# IMU_07_21_2017.net
KiCad netlist of a schematic drawn in EAGLE
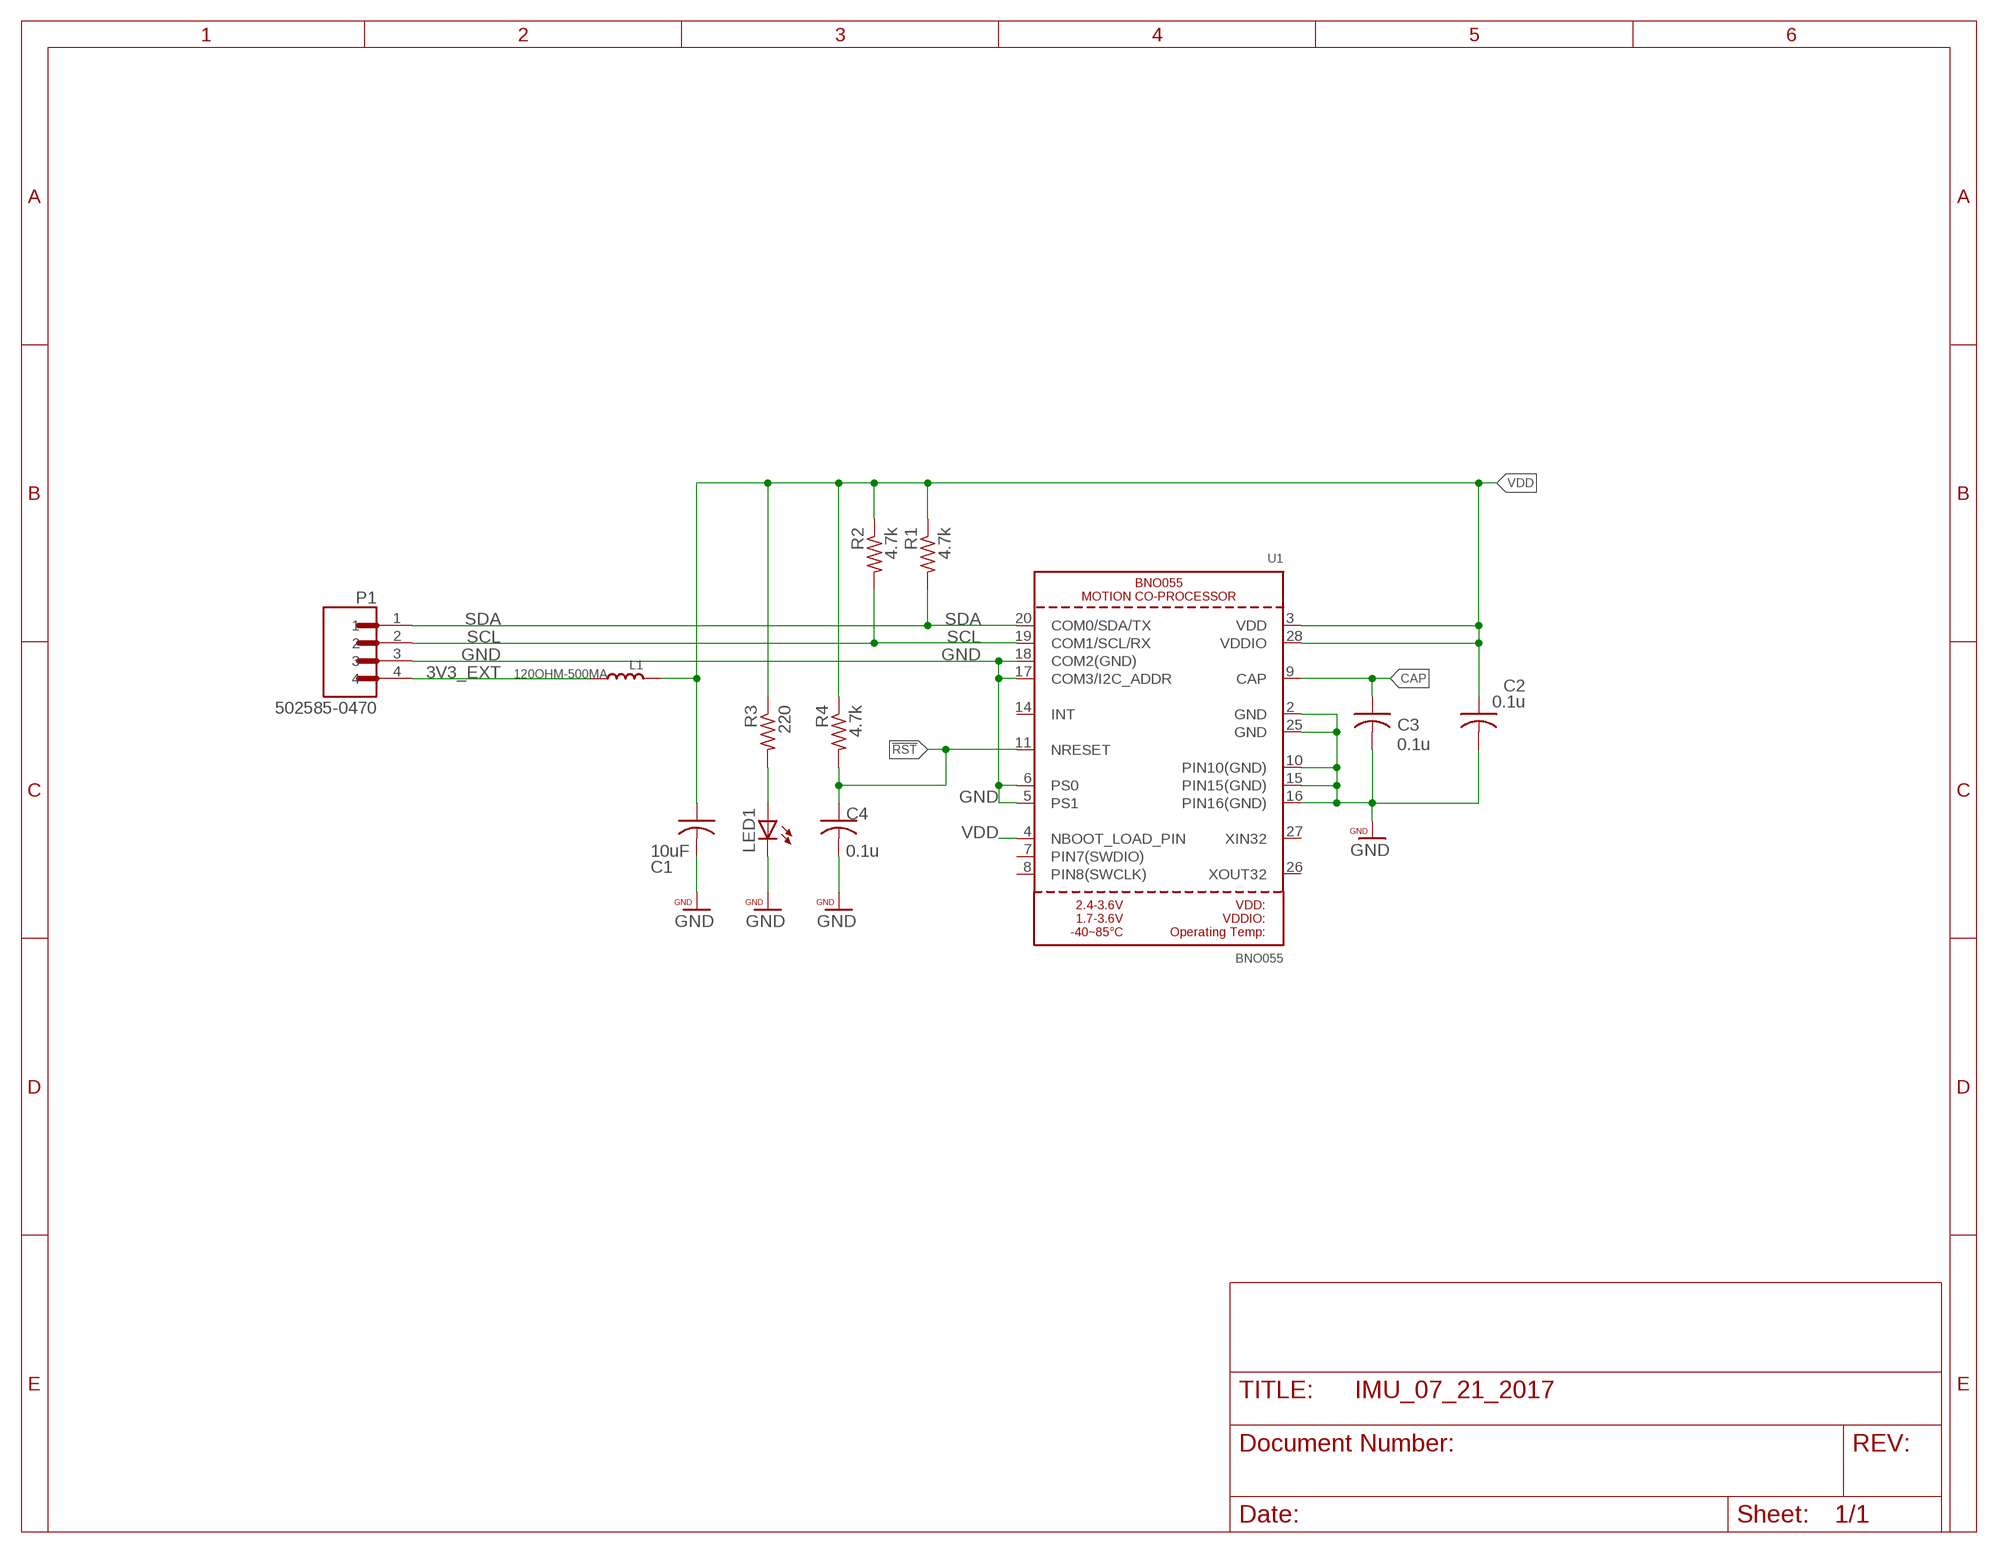
[diagram p0: schematic, sheet 1]

(export (version "E")
  (design (tool "Eeschema 10.0.6"))
  (components
    (comp (ref "C1")
      (value "10uF")
      (footprint "eagle-import:C0402")
      (libsource (lib "eagle-import") (part "C-USC0402"))
    )
    (comp (ref "C2")
      (value "0.1u")
      (footprint "eagle-import:C0402")
      (libsource (lib "eagle-import") (part "C-USC0402"))
    )
    (comp (ref "C3")
      (value "0.1u")
      (footprint "eagle-import:C0402")
      (libsource (lib "eagle-import") (part "C-USC0402"))
    )
    (comp (ref "C4")
      (value "0.1u")
      (footprint "eagle-import:C0402")
      (libsource (lib "eagle-import") (part "C-USC0402"))
    )
    (comp (ref "L1")
      (value "120OHM-500MA")
      (footprint "eagle-import:L0603")
      (fields (field (name "MPN") "BLM18AG121SN1D"))
      (libsource (lib "eagle-import") (part "SMD-FERRITE-CHIP-120-OHM-500MA(0603)"))
    )
    (comp (ref "LED1")
      (value "LEDCHIP-LED0603")
      (footprint "eagle-import:CHIP-LED0603")
      (libsource (lib "eagle-import") (part "LEDCHIP-LED0603"))
    )
    (comp (ref "P1")
      (value "502585-0470")
      (footprint "eagle-import:MOLEX_502585-0470")
      (fields (field (name "MF") "Molex"))
      (libsource (lib "eagle-import") (part "502585-0470"))
    )
    (comp (ref "R1")
      (value "4.7k")
      (footprint "eagle-import:R0402")
      (libsource (lib "eagle-import") (part "R-US_R0402"))
    )
    (comp (ref "R2")
      (value "4.7k")
      (footprint "eagle-import:R0402")
      (libsource (lib "eagle-import") (part "R-US_R0402"))
    )
    (comp (ref "R3")
      (value "220")
      (footprint "eagle-import:R0402")
      (libsource (lib "eagle-import") (part "R-US_R0402"))
    )
    (comp (ref "R4")
      (value "4.7k")
      (footprint "eagle-import:R0402")
      (libsource (lib "eagle-import") (part "R-US_R0402"))
    )
    (comp (ref "U1")
      (value "BNO055")
      (footprint "eagle-import:BNO055")
      (libsource (lib "eagle-import") (part "BNO055"))
    )
  )
  (nets
    (net (code "1") (name "/3V3_EXT") (class "Default")
      (node (ref "L1") (pin "2") (pinfunction "2_2") (pintype "passive"))
      (node (ref "P1") (pin "4") (pinfunction "4_4") (pintype "passive"))
    )
    (net (code "2") (name "/SCL") (class "Default")
      (node (ref "P1") (pin "2") (pinfunction "2_2") (pintype "passive"))
      (node (ref "R2") (pin "2") (pinfunction "2_2") (pintype "passive"))
      (node (ref "U1") (pin "19") (pinfunction "COM1/SCL/RX_19") (pintype "bidirectional"))
    )
    (net (code "3") (name "/SDA") (class "Default")
      (node (ref "P1") (pin "1") (pinfunction "1_1") (pintype "passive"))
      (node (ref "R1") (pin "2") (pinfunction "2_2") (pintype "passive"))
      (node (ref "U1") (pin "20") (pinfunction "COM0/SDA/TX_20") (pintype "bidirectional"))
    )
    (net (code "4") (name "/~{RST}") (class "Default")
      (node (ref "C4") (pin "1") (pinfunction "1_1") (pintype "passive"))
      (node (ref "R4") (pin "2") (pinfunction "2_2") (pintype "passive"))
      (node (ref "U1") (pin "11") (pinfunction "NRESET_11") (pintype "bidirectional"))
    )
    (net (code "5") (name "CAP") (class "Default")
      (node (ref "C3") (pin "1") (pinfunction "1_1") (pintype "passive"))
      (node (ref "U1") (pin "9") (pinfunction "CAP_9") (pintype "passive"))
    )
    (net (code "6") (name "GND") (class "Default")
      (node (ref "C1") (pin "2") (pinfunction "2_2") (pintype "passive"))
      (node (ref "C2") (pin "2") (pinfunction "2_2") (pintype "passive"))
      (node (ref "C3") (pin "2") (pinfunction "2_2") (pintype "passive"))
      (node (ref "C4") (pin "2") (pinfunction "2_2") (pintype "passive"))
      (node (ref "LED1") (pin "C") (pinfunction "C_C") (pintype "passive"))
      (node (ref "P1") (pin "3") (pinfunction "3_3") (pintype "passive"))
      (node (ref "U1") (pin "10") (pinfunction "PIN10(GND)_10") (pintype "bidirectional"))
      (node (ref "U1") (pin "15") (pinfunction "PIN15(GND)_15") (pintype "bidirectional"))
      (node (ref "U1") (pin "16") (pinfunction "PIN16(GND)_16") (pintype "bidirectional"))
      (node (ref "U1") (pin "17") (pinfunction "COM3/I2C_ADDR_17") (pintype "bidirectional"))
      (node (ref "U1") (pin "18") (pinfunction "COM2(GND)_18") (pintype "bidirectional"))
      (node (ref "U1") (pin "2") (pinfunction "GND_2") (pintype "power_in"))
      (node (ref "U1") (pin "25") (pinfunction "GND_25") (pintype "power_in"))
      (node (ref "U1") (pin "5") (pinfunction "PS1_5") (pintype "input"))
      (node (ref "U1") (pin "6") (pinfunction "PS0_6") (pintype "input"))
    )
    (net (code "7") (name "Net-(LED1-PadA)") (class "Default")
      (node (ref "LED1") (pin "A") (pinfunction "A_A") (pintype "passive"))
      (node (ref "R3") (pin "2") (pinfunction "2_2") (pintype "passive"))
    )
    (net (code "8") (name "VDD") (class "Default")
      (node (ref "C1") (pin "1") (pinfunction "1_1") (pintype "passive"))
      (node (ref "C2") (pin "1") (pinfunction "1_1") (pintype "passive"))
      (node (ref "L1") (pin "1") (pinfunction "1_1") (pintype "passive"))
      (node (ref "R1") (pin "1") (pinfunction "1_1") (pintype "passive"))
      (node (ref "R2") (pin "1") (pinfunction "1_1") (pintype "passive"))
      (node (ref "R3") (pin "1") (pinfunction "1_1") (pintype "passive"))
      (node (ref "R4") (pin "1") (pinfunction "1_1") (pintype "passive"))
      (node (ref "U1") (pin "28") (pinfunction "VDDIO_28") (pintype "power_in"))
      (node (ref "U1") (pin "3") (pinfunction "VDD_3") (pintype "power_in"))
      (node (ref "U1") (pin "4") (pinfunction "NBOOT_LOAD_PIN_4") (pintype "bidirectional"))
    )
    (net (code "9") (name "unconnected-(U1-INT-Pad14)") (class "Default")
      (node (ref "U1") (pin "14") (pinfunction "INT_14") (pintype "output"))
    )
    (net (code "10") (name "unconnected-(U1-PIN7(SWDIO)-Pad7)") (class "Default")
      (node (ref "U1") (pin "7") (pinfunction "PIN7(SWDIO)_7") (pintype "bidirectional"))
    )
    (net (code "11") (name "unconnected-(U1-PIN8(SWCLK)-Pad8)") (class "Default")
      (node (ref "U1") (pin "8") (pinfunction "PIN8(SWCLK)_8") (pintype "bidirectional"))
    )
    (net (code "12") (name "unconnected-(U1-XIN32-Pad27)") (class "Default")
      (node (ref "U1") (pin "27") (pinfunction "XIN32_27") (pintype "input"))
    )
    (net (code "13") (name "unconnected-(U1-XOUT32-Pad26)") (class "Default")
      (node (ref "U1") (pin "26") (pinfunction "XOUT32_26") (pintype "output"))
    )
  )
)
